# 202011AWSNP01.net
KiCad netlist of a schematic drawn in Altium Designer
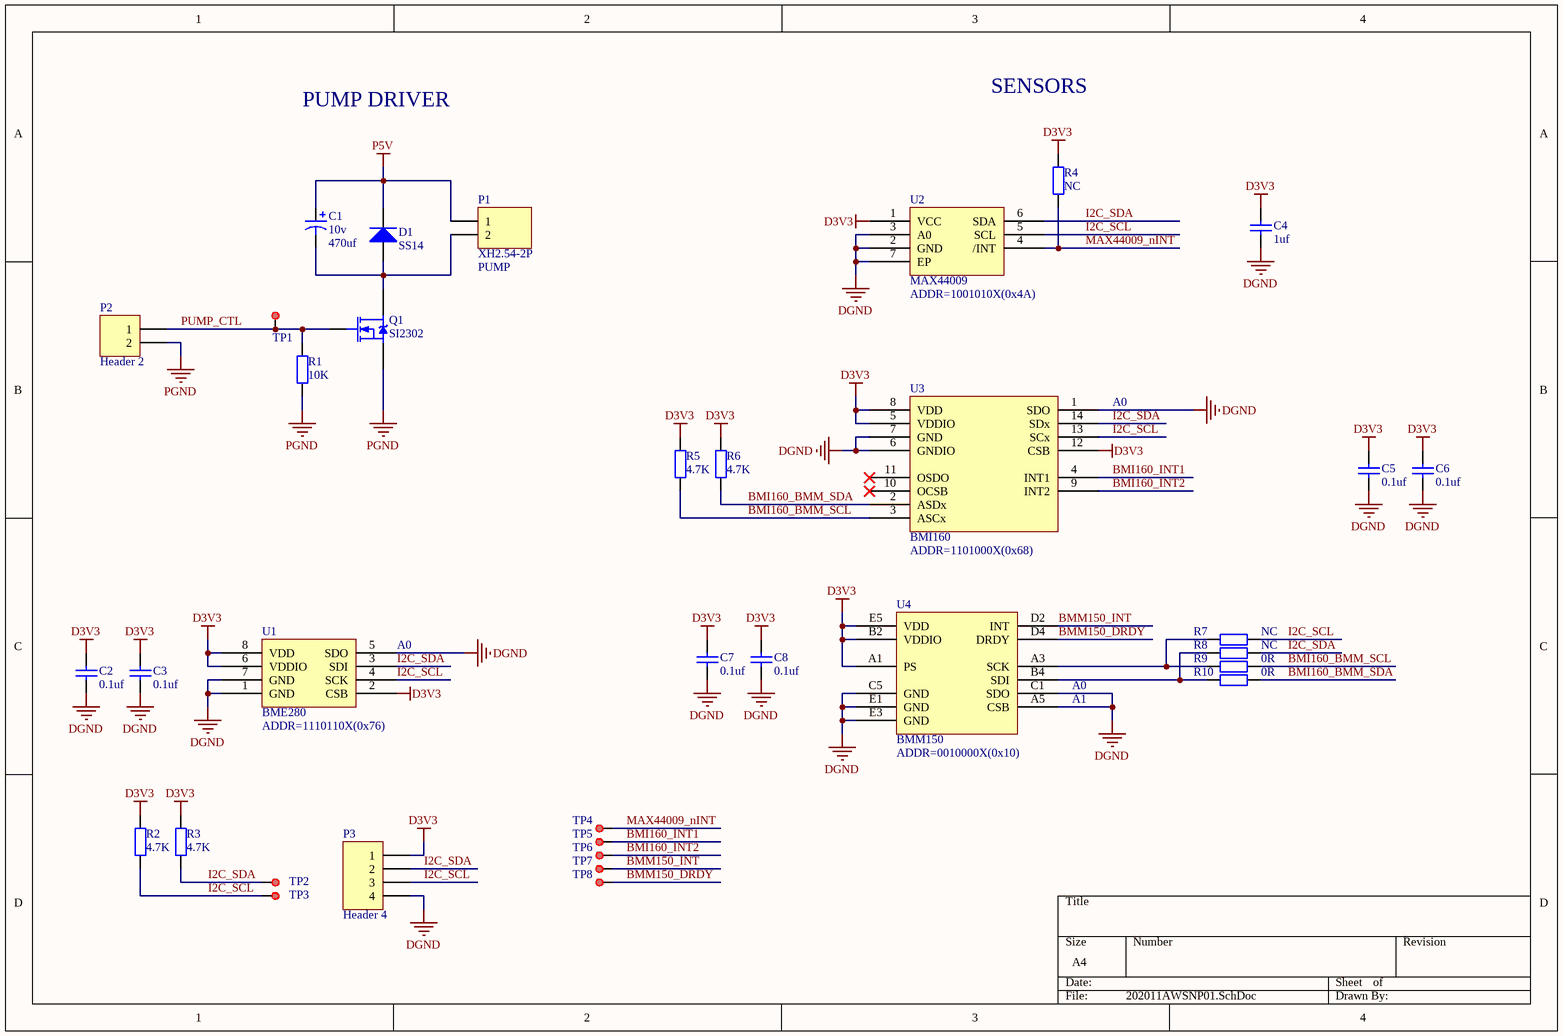
[diagram p0: 202011AWSNP01.SchDoc]

(export (version "E")
  (design (tool "Eeschema 10.0.6"))
  (components
    (comp (ref "C1")
      (value "470uf")
      (footprint "C6.3X7.7-SMD")
      (fields (field (name "VOLTAGE") "10v") (field (name "Comment") "Cap2"))
      (libsource (lib "carrot_lib") (part "Cap2"))
    )
    (comp (ref "C2")
      (value "0.1uf")
      (footprint "C0603")
      (fields (field (name "Comment") "Cap"))
      (libsource (lib "carrot_lib") (part "Cap"))
    )
    (comp (ref "C3")
      (value "0.1uf")
      (footprint "C0603")
      (fields (field (name "Comment") "Cap"))
      (libsource (lib "carrot_lib") (part "Cap"))
    )
    (comp (ref "C4")
      (value "1uf")
      (footprint "C0603")
      (fields (field (name "Comment") "Cap"))
      (libsource (lib "carrot_lib") (part "Cap"))
    )
    (comp (ref "C5")
      (value "0.1uf")
      (footprint "C0603")
      (fields (field (name "Comment") "Cap"))
      (libsource (lib "carrot_lib") (part "Cap"))
    )
    (comp (ref "C6")
      (value "0.1uf")
      (footprint "C0603")
      (fields (field (name "Comment") "Cap"))
      (libsource (lib "carrot_lib") (part "Cap"))
    )
    (comp (ref "C7")
      (value "0.1uf")
      (footprint "C0603")
      (fields (field (name "Comment") "Cap"))
      (libsource (lib "carrot_lib") (part "Cap"))
    )
    (comp (ref "C8")
      (value "0.1uf")
      (footprint "C0603")
      (fields (field (name "Comment") "Cap"))
      (libsource (lib "carrot_lib") (part "Cap"))
    )
    (comp (ref "D1")
      (value "SS14")
      (footprint "SMA/DO-214AC")
      (fields (field (name "Comment") "Diode"))
      (libsource (lib "carrot_lib") (part "Diode"))
    )
    (comp (ref "P1")
      (value "XH2.54-2P")
      (footprint "XH2.54-2P")
      (libsource (lib "carrot_lib") (part "XH2.54-2P"))
    )
    (comp (ref "P2")
      (value "Header 2")
      (footprint "HDR1X2")
      (description "Header, 2-Pin")
      (fields (field (name "PUBLISHER") "Altium Limited"))
      (libsource (lib "Miscellaneous Connectors") (part "Header 2"))
    )
    (comp (ref "P3")
      (value "Header 4")
      (footprint "HDR1X4")
      (description "Header, 4-Pin")
      (fields (field (name "PUBLISHER") "Altium Limited"))
      (libsource (lib "Miscellaneous Connectors") (part "Header 4"))
    )
    (comp (ref "Q1")
      (value "SI2302")
      (footprint "SI2302-SOT23")
      (description "N-Channel 20 V (D-S) MOSFET")
      (libsource (lib "carrot_lib") (part "SI2302"))
    )
    (comp (ref "R1")
      (value "10K")
      (footprint "R0805")
      (description "电阻")
      (fields (field (name "Comment") "Res"))
      (libsource (lib "carrot_lib") (part "Res"))
    )
    (comp (ref "R2")
      (value "4.7K")
      (footprint "R0603")
      (description "电阻")
      (fields (field (name "Comment") "Res"))
      (libsource (lib "carrot_lib") (part "Res"))
    )
    (comp (ref "R3")
      (value "4.7K")
      (footprint "R0603")
      (description "电阻")
      (fields (field (name "Comment") "Res"))
      (libsource (lib "carrot_lib") (part "Res"))
    )
    (comp (ref "R4")
      (value "NC")
      (footprint "R0603")
      (description "电阻")
      (fields (field (name "Comment") "Res"))
      (libsource (lib "carrot_lib") (part "Res"))
    )
    (comp (ref "R5")
      (value "4.7K")
      (footprint "R0603")
      (description "电阻")
      (fields (field (name "Comment") "Res"))
      (libsource (lib "carrot_lib") (part "Res"))
    )
    (comp (ref "R6")
      (value "4.7K")
      (footprint "R0603")
      (description "电阻")
      (fields (field (name "Comment") "Res"))
      (libsource (lib "carrot_lib") (part "Res"))
    )
    (comp (ref "R7")
      (value "NC")
      (footprint "R0603")
      (description "电阻")
      (fields (field (name "Comment") "Res"))
      (libsource (lib "") (part "Res_1"))
    )
    (comp (ref "R8")
      (value "NC")
      (footprint "R0603")
      (description "电阻")
      (fields (field (name "Comment") "Res"))
      (libsource (lib "") (part "Res_1"))
    )
    (comp (ref "R9")
      (value "0R")
      (footprint "R0603")
      (description "电阻")
      (fields (field (name "Comment") "Res"))
      (libsource (lib "") (part "Res_1"))
    )
    (comp (ref "R10")
      (value "0R")
      (footprint "R0603")
      (description "电阻")
      (fields (field (name "Comment") "Res"))
      (libsource (lib "") (part "Res_1"))
    )
    (comp (ref "TP1")
      (value "TestPoint")
      (footprint "TestPoint-R30")
      (description "测试点")
      (libsource (lib "carrot_lib") (part "TestPoint"))
    )
    (comp (ref "TP2")
      (value "TestPoint")
      (footprint "TestPoint-R30")
      (description "测试点")
      (libsource (lib "carrot_lib") (part "TestPoint"))
    )
    (comp (ref "TP3")
      (value "TestPoint")
      (footprint "TestPoint-R30")
      (description "测试点")
      (libsource (lib "carrot_lib") (part "TestPoint"))
    )
    (comp (ref "TP4")
      (value "TestPoint")
      (footprint "TestPoint-R30")
      (description "测试点")
      (libsource (lib "carrot_lib") (part "TestPoint"))
    )
    (comp (ref "TP5")
      (value "TestPoint")
      (footprint "TestPoint-R30")
      (description "测试点")
      (libsource (lib "carrot_lib") (part "TestPoint"))
    )
    (comp (ref "TP6")
      (value "TestPoint")
      (footprint "TestPoint-R30")
      (description "测试点")
      (libsource (lib "carrot_lib") (part "TestPoint"))
    )
    (comp (ref "TP7")
      (value "TestPoint")
      (footprint "TestPoint-R30")
      (description "测试点")
      (libsource (lib "carrot_lib") (part "TestPoint"))
    )
    (comp (ref "TP8")
      (value "TestPoint")
      (footprint "TestPoint-R30")
      (description "测试点")
      (libsource (lib "carrot_lib") (part "TestPoint"))
    )
    (comp (ref "U1")
      (value "BME280")
      (footprint "BME280-LGA8")
      (description "Combined humidity and pressure sensor")
      (libsource (lib "carrot_lib") (part "BME280"))
    )
    (comp (ref "U2")
      (value "MAX44009")
      (footprint "MAX44009-UTDFN6")
      (description "Industry’s Lowest-Power Ambient Light Sensor with ADC")
      (libsource (lib "carrot_lib") (part "MAX44009"))
    )
    (comp (ref "U3")
      (value "BMI160")
      (footprint "BMI160-LGA14")
      (description "Small, low-power Inertial Measurement Unit")
      (libsource (lib "carrot_lib") (part "BMI160"))
    )
    (comp (ref "U4")
      (value "BMM150")
      (footprint "BMM150-BGA12+")
      (description "THREE-AXIS GEOMAGNETIC SENSOR")
      (libsource (lib "carrot_lib") (part "BMM150"))
    )
  )
  (nets
    (net (code "1") (name "/BMI160_BMM_SCL") (class "Default")
      (node (ref "R5") (pin "1") (pinfunction "1_1") (pintype "passive"))
      (node (ref "R9") (pin "1") (pinfunction "1_1") (pintype "passive"))
      (node (ref "U3") (pin "3") (pinfunction "ASCx_3") (pintype "passive"))
    )
    (net (code "2") (name "/BMI160_BMM_SDA") (class "Default")
      (node (ref "R10") (pin "1") (pinfunction "1_1") (pintype "passive"))
      (node (ref "R6") (pin "1") (pinfunction "1_1") (pintype "passive"))
      (node (ref "U3") (pin "2") (pinfunction "ASDx_2") (pintype "passive"))
    )
    (net (code "3") (name "/BMI160_INT1") (class "Default")
      (node (ref "TP5") (pin "1") (pinfunction "1_1") (pintype "passive"))
      (node (ref "U3") (pin "4") (pinfunction "INT1_4") (pintype "passive"))
    )
    (net (code "4") (name "/BMI160_INT2") (class "Default")
      (node (ref "TP6") (pin "1") (pinfunction "1_1") (pintype "passive"))
      (node (ref "U3") (pin "9") (pinfunction "INT2_9") (pintype "passive"))
    )
    (net (code "5") (name "/BMM150_DRDY") (class "Default")
      (node (ref "TP8") (pin "1") (pinfunction "1_1") (pintype "passive"))
      (node (ref "U4") (pin "D4") (pinfunction "DRDY_D4") (pintype "passive"))
    )
    (net (code "6") (name "/BMM150_INT") (class "Default")
      (node (ref "TP7") (pin "1") (pinfunction "1_1") (pintype "passive"))
      (node (ref "U4") (pin "D2") (pinfunction "INT_D2") (pintype "passive"))
    )
    (net (code "7") (name "/I2C_SCL") (class "Default")
      (node (ref "P3") (pin "3") (pinfunction "3_3") (pintype "passive"))
      (node (ref "R2") (pin "1") (pinfunction "1_1") (pintype "passive"))
      (node (ref "R7") (pin "1") (pinfunction "1_1") (pintype "passive"))
      (node (ref "TP3") (pin "1") (pinfunction "1_1") (pintype "passive"))
      (node (ref "U1") (pin "4") (pinfunction "SCK_4") (pintype "passive"))
      (node (ref "U2") (pin "5") (pinfunction "SCL_5") (pintype "passive"))
      (node (ref "U3") (pin "13") (pinfunction "SCx_13") (pintype "passive"))
    )
    (net (code "8") (name "/I2C_SDA") (class "Default")
      (node (ref "P3") (pin "2") (pinfunction "2_2") (pintype "passive"))
      (node (ref "R3") (pin "1") (pinfunction "1_1") (pintype "passive"))
      (node (ref "R8") (pin "1") (pinfunction "1_1") (pintype "passive"))
      (node (ref "TP2") (pin "1") (pinfunction "1_1") (pintype "passive"))
      (node (ref "U1") (pin "3") (pinfunction "SDI_3") (pintype "passive"))
      (node (ref "U2") (pin "6") (pinfunction "SDA_6") (pintype "passive"))
      (node (ref "U3") (pin "14") (pinfunction "SDx_14") (pintype "passive"))
    )
    (net (code "9") (name "/MAX44009_nINT") (class "Default")
      (node (ref "R4") (pin "1") (pinfunction "1_1") (pintype "passive"))
      (node (ref "TP4") (pin "1") (pinfunction "1_1") (pintype "passive"))
      (node (ref "U2") (pin "4") (pinfunction "/INT_4") (pintype "passive"))
    )
    (net (code "10") (name "/PUMP_CTL") (class "Default")
      (node (ref "P2") (pin "1") (pinfunction "1_1") (pintype "passive"))
      (node (ref "Q1") (pin "1") (pinfunction "G_1") (pintype "passive"))
      (node (ref "R1") (pin "2") (pinfunction "2_2") (pintype "passive"))
      (node (ref "TP1") (pin "1") (pinfunction "1_1") (pintype "passive"))
    )
    (net (code "11") (name "D3V3") (class "Default")
      (node (ref "C2") (pin "2") (pinfunction "2_2") (pintype "passive"))
      (node (ref "C3") (pin "2") (pinfunction "2_2") (pintype "passive"))
      (node (ref "C4") (pin "1") (pinfunction "1_1") (pintype "passive"))
      (node (ref "C5") (pin "2") (pinfunction "2_2") (pintype "passive"))
      (node (ref "C6") (pin "2") (pinfunction "2_2") (pintype "passive"))
      (node (ref "C7") (pin "2") (pinfunction "2_2") (pintype "passive"))
      (node (ref "C8") (pin "2") (pinfunction "2_2") (pintype "passive"))
      (node (ref "P3") (pin "1") (pinfunction "1_1") (pintype "passive"))
      (node (ref "R2") (pin "2") (pinfunction "2_2") (pintype "passive"))
      (node (ref "R3") (pin "2") (pinfunction "2_2") (pintype "passive"))
      (node (ref "R4") (pin "2") (pinfunction "2_2") (pintype "passive"))
      (node (ref "R5") (pin "2") (pinfunction "2_2") (pintype "passive"))
      (node (ref "R6") (pin "2") (pinfunction "2_2") (pintype "passive"))
      (node (ref "U1") (pin "2") (pinfunction "CSB_2") (pintype "passive"))
      (node (ref "U1") (pin "6") (pinfunction "VDDIO_6") (pintype "passive"))
      (node (ref "U1") (pin "8") (pinfunction "VDD_8") (pintype "passive"))
      (node (ref "U2") (pin "1") (pinfunction "VCC_1") (pintype "passive"))
      (node (ref "U3") (pin "12") (pinfunction "CSB_12") (pintype "passive"))
      (node (ref "U3") (pin "5") (pinfunction "VDDIO_5") (pintype "passive"))
      (node (ref "U3") (pin "8") (pinfunction "VDD_8") (pintype "passive"))
      (node (ref "U4") (pin "A1") (pinfunction "PS_A1") (pintype "passive"))
      (node (ref "U4") (pin "B2") (pinfunction "VDDIO_B2") (pintype "passive"))
      (node (ref "U4") (pin "E5") (pinfunction "VDD_E5") (pintype "passive"))
    )
    (net (code "12") (name "DGND") (class "Default")
      (node (ref "C2") (pin "1") (pinfunction "1_1") (pintype "passive"))
      (node (ref "C3") (pin "1") (pinfunction "1_1") (pintype "passive"))
      (node (ref "C4") (pin "2") (pinfunction "2_2") (pintype "passive"))
      (node (ref "C5") (pin "1") (pinfunction "1_1") (pintype "passive"))
      (node (ref "C6") (pin "1") (pinfunction "1_1") (pintype "passive"))
      (node (ref "C7") (pin "1") (pinfunction "1_1") (pintype "passive"))
      (node (ref "C8") (pin "1") (pinfunction "1_1") (pintype "passive"))
      (node (ref "P3") (pin "4") (pinfunction "4_4") (pintype "passive"))
      (node (ref "U1") (pin "1") (pinfunction "GND_1") (pintype "passive"))
      (node (ref "U1") (pin "5") (pinfunction "SDO_5") (pintype "passive"))
      (node (ref "U1") (pin "7") (pinfunction "GND_7") (pintype "passive"))
      (node (ref "U2") (pin "2") (pinfunction "GND_2") (pintype "passive"))
      (node (ref "U2") (pin "3") (pinfunction "A0_3") (pintype "passive"))
      (node (ref "U2") (pin "7") (pinfunction "EP_7") (pintype "passive"))
      (node (ref "U3") (pin "1") (pinfunction "SDO_1") (pintype "passive"))
      (node (ref "U3") (pin "6") (pinfunction "GNDIO_6") (pintype "passive"))
      (node (ref "U3") (pin "7") (pinfunction "GND_7") (pintype "passive"))
      (node (ref "U4") (pin "A5") (pinfunction "CSB_A5") (pintype "passive"))
      (node (ref "U4") (pin "C1") (pinfunction "SDO_C1") (pintype "passive"))
      (node (ref "U4") (pin "C5") (pinfunction "GND_C5") (pintype "passive"))
      (node (ref "U4") (pin "E1") (pinfunction "GND_E1") (pintype "passive"))
      (node (ref "U4") (pin "E3") (pinfunction "GND_E3") (pintype "passive"))
    )
    (net (code "13") (name "Net-(D1-A)") (class "Default")
      (node (ref "C1") (pin "2") (pinfunction "2_2") (pintype "passive"))
      (node (ref "D1") (pin "1") (pinfunction "A_1") (pintype "passive"))
      (node (ref "P1") (pin "2") (pinfunction "2_2") (pintype "passive"))
      (node (ref "Q1") (pin "3") (pinfunction "D_3") (pintype "passive"))
    )
    (net (code "14") (name "Net-(U4-SCK)") (class "Default")
      (node (ref "R7") (pin "2") (pinfunction "2_2") (pintype "passive"))
      (node (ref "R9") (pin "2") (pinfunction "2_2") (pintype "passive"))
      (node (ref "U4") (pin "A3") (pinfunction "SCK_A3") (pintype "passive"))
    )
    (net (code "15") (name "Net-(U4-SDI)") (class "Default")
      (node (ref "R10") (pin "2") (pinfunction "2_2") (pintype "passive"))
      (node (ref "R8") (pin "2") (pinfunction "2_2") (pintype "passive"))
      (node (ref "U4") (pin "B4") (pinfunction "SDI_B4") (pintype "passive"))
    )
    (net (code "16") (name "P5V") (class "Default")
      (node (ref "C1") (pin "1") (pinfunction "1_1") (pintype "passive"))
      (node (ref "D1") (pin "2") (pinfunction "K_2") (pintype "passive"))
      (node (ref "P1") (pin "1") (pinfunction "1_1") (pintype "passive"))
    )
    (net (code "17") (name "PGND") (class "Default")
      (node (ref "P2") (pin "2") (pinfunction "2_2") (pintype "passive"))
      (node (ref "Q1") (pin "2") (pinfunction "S_2") (pintype "passive"))
      (node (ref "R1") (pin "1") (pinfunction "1_1") (pintype "passive"))
    )
    (net (code "18") (name "unconnected-(U3-OCSB-Pad10)") (class "Default")
      (node (ref "U3") (pin "10") (pinfunction "OCSB_10") (pintype "passive+no_connect"))
    )
    (net (code "19") (name "unconnected-(U3-OSDO-Pad11)") (class "Default")
      (node (ref "U3") (pin "11") (pinfunction "OSDO_11") (pintype "passive+no_connect"))
    )
  )
)
